# Flyback.net
KiCad netlist of a schematic drawn in Altium Designer
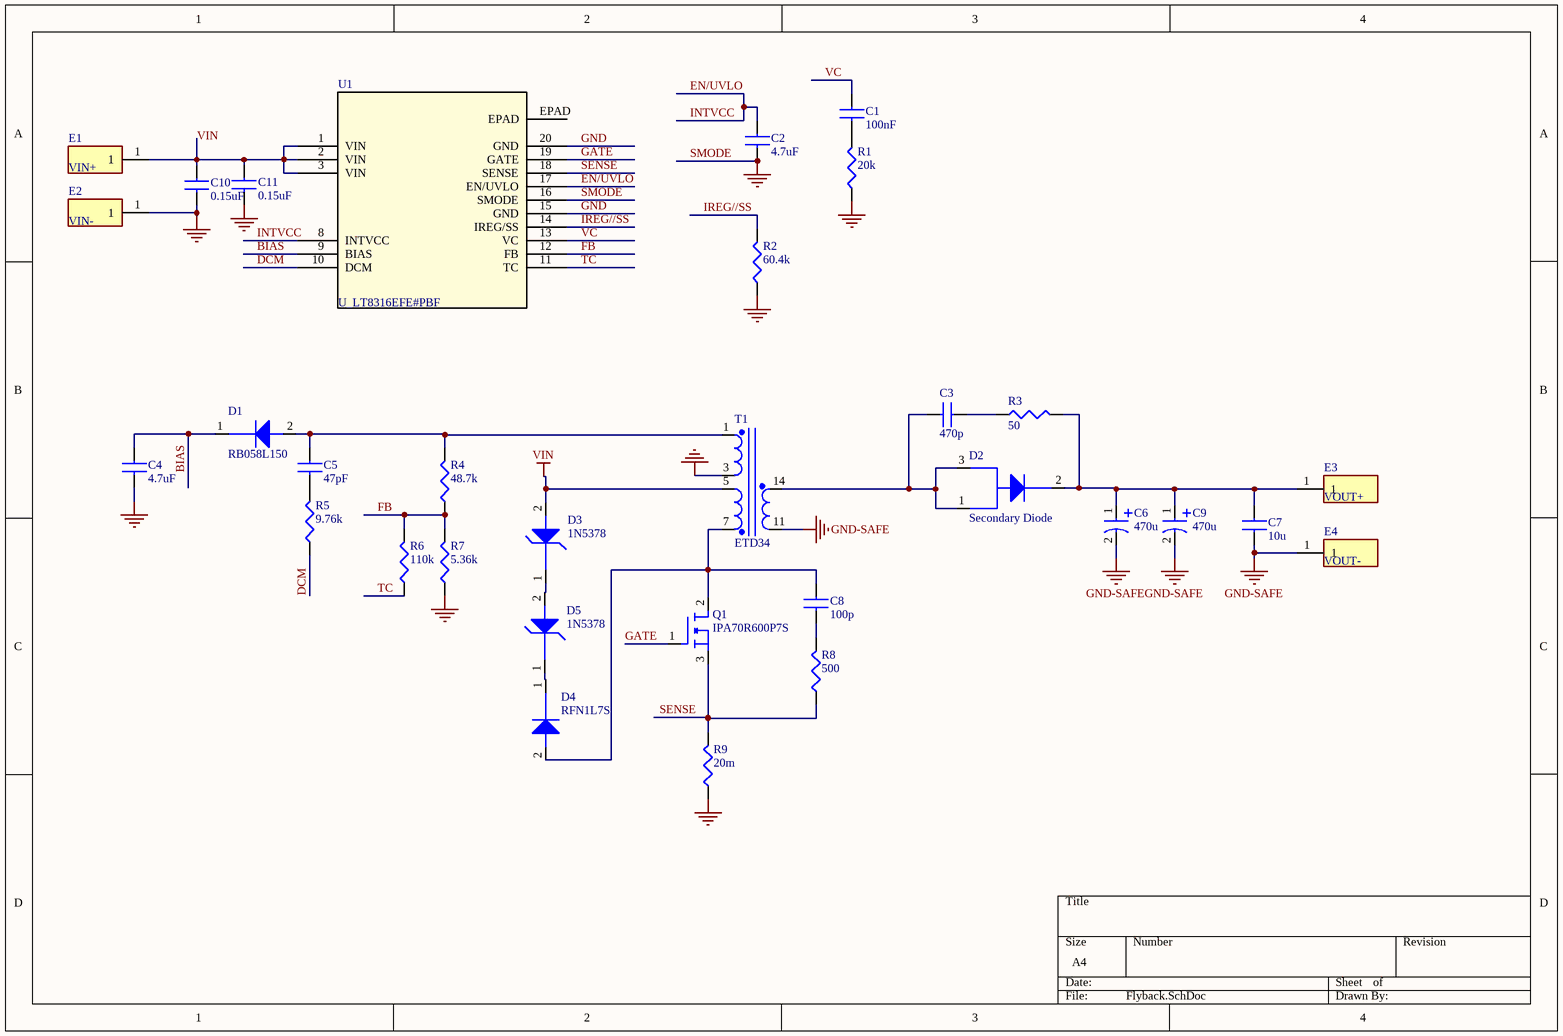
[diagram p0: Flyback.SchDoc]

(export (version "E")
  (design (tool "Eeschema 10.0.6"))
  (components
    (comp (ref "C1")
      (value "100nF")
      (footprint "C0402")
      (description "CAP CER 0.1UF 25V X7R 0402\r\nGRM155R71E104KE14J")
      (fields
        (field (name "MANUFACTURER") "Murata")
        (field (name "MANUFACTURER PART NUMBER") "GRM155R71E104KE14J")
      )
      (libsource (lib "Flyback_Schlib") (part "C_Vc"))
    )
    (comp (ref "C2")
      (value "4.7uF")
      (footprint "C0805")
      (description "CAP CER 4.7UF 25V X5R 0805\r\nGRM219R61E475MA73D")
      (fields
        (field (name "MANUFACTURER") "Murata")
        (field (name "MANUFACTURER PART NUMBER") "GRM219R61E475MA73D")
      )
      (libsource (lib "Flyback_Schlib") (part "C_IntVcc"))
    )
    (comp (ref "C3")
      (value "470p")
      (footprint "C0402")
      (description "Cap Ceramic 470pF 100V X7R 10% SMD 0402 125C Paper T/R\r\nGRM155R72A471KA01D")
      (fields
        (field (name "MANUFACTURER") "Murata")
        (field (name "MANUFACTURER PART NUMBER") "GRM155R72A471KA01D")
      )
      (libsource (lib "Flyback_Schlib") (part "C_Snub_Sec"))
    )
    (comp (ref "C4")
      (value "4.7uF")
      (footprint "C0805")
      (description "CAP CER 4.7UF 35V 10% X5R 0805\r\nGRM219R6YA475KA73D")
      (fields
        (field (name "MANUFACTURER") "Murata")
        (field (name "MANUFACTURER PART NUMBER") "GRM219R6YA475KA73D")
      )
      (libsource (lib "Flyback_Schlib") (part "C_Bias"))
    )
    (comp (ref "C5")
      (value "47pF")
      (footprint "C0603")
      (fields
        (field (name "MANUFACTURER") "Murata")
        (field (name "MANUFACTURER PART NUMBER") "GRM1885C2A470JA01D")
        (field (name "TOLERANCE") "5%")
      )
      (libsource (lib "Flyback_Schlib") (part "C_DCM"))
    )
    (comp (ref "C6")
      (value "470u")
      (footprint "C6.3x12")
      (description "Solid Polymer Aluminum, Radial, Output Capacitor\r\nA750EQ477M1CAAE015")
      (fields
        (field (name "MANUFACTURER") "KEMET")
        (field (name "MANUFACTURER PART NUMBER") "A750EQ477M1CAAE015")
      )
      (libsource (lib "Flyback_Schlib") (part "C_OUT_470u"))
    )
    (comp (ref "C7")
      (value "10u")
      (footprint "C0805")
      (fields
        (field (name "MANUFACTURER") "Murata")
        (field (name "MANUFACTURER PART NUMBER") "GRM21BR61E106MA73L")
        (field (name "TOLERANCE") "20%")
      )
      (libsource (lib "Flyback_Schlib") (part "C_OUT_10u"))
    )
    (comp (ref "C8")
      (value "100p")
      (footprint "C1206")
      (description "CAP CER 100PF 630V C0G/NP0 1206\r\nGRM31A5C2J101JW01D")
      (fields
        (field (name "MANUFACTURER") "Murata")
        (field (name "MANUFACTURER PART NUMBER") "GRM31A5C2J101JW01D")
      )
      (libsource (lib "Flyback_Schlib") (part "C_Snub_Pri"))
    )
    (comp (ref "C9")
      (value "470u")
      (footprint "C6.3x12")
      (description "Solid Polymer Aluminum, Radial, Output Capacitor\r\nA750EQ477M1CAAE015")
      (fields
        (field (name "MANUFACTURER") "KEMET")
        (field (name "MANUFACTURER PART NUMBER") "A750EQ477M1CAAE015")
      )
      (libsource (lib "Flyback_Schlib") (part "C_OUT_470u"))
    )
    (comp (ref "C10")
      (value "0.15uF")
      (footprint "C1210")
      (description "CAP CER 0.15UF 500V X7R 1210\r\nC1210C154KCRACTU")
      (fields
        (field (name "MANUFACTURER") "KEMET")
        (field (name "MANUFACTURER PART NUMBER") "C1210C154KCRACTU")
      )
      (libsource (lib "Flyback_Schlib") (part "C_Input"))
    )
    (comp (ref "C11")
      (value "0.15uF")
      (footprint "C1210")
      (description "CAP CER 0.15UF 500V X7R 1210\r\nC1210C154KCRACTU")
      (fields
        (field (name "MANUFACTURER") "KEMET")
        (field (name "MANUFACTURER PART NUMBER") "C1210C154KCRACTU")
      )
      (libsource (lib "Flyback_Schlib") (part "C_Input"))
    )
    (comp (ref "D1")
      (value "RB058L150")
      (footprint "SOD128")
      (description "Schottky Barrier Diode for general rectification Diode for Bias Pin")
      (fields (field (name "MANUFACTURER") "Rohm") (field (name "MANUFACTURER PART NUMBER") "RB058LAM150TR"))
      (libsource (lib "Flyback_Schlib") (part "D_RB058LAM150TR"))
    )
    (comp (ref "D2")
      (value "Secondary Diode")
      (footprint "TO220AB")
      (description "Diode Schottky 120V 20A 3-Pin(3+Tab) TO-220AB Tube")
      (fields
        (field (name "MANUFACTURER") "STMicroelectronics")
        (field (name "MANUFACTURER PART NUMBER") "STPS20SM120ST")
      )
      (libsource (lib "Flyback_Schlib") (part "D_STPS20SM120ST"))
    )
    (comp (ref "D3")
      (value "1N5378")
      (footprint "D017AA")
      (description "DIODE ZENER 100V 5W AXIAL\r\n1N5378BG")
      (fields
        (field (name "MANUFACTURER") "ON Semiconductor")
        (field (name "MANUFACTURER PART NUMBER") "1N5378BG")
      )
      (libsource (lib "Flyback_Schlib") (part "D_1N5378BG"))
    )
    (comp (ref "D4")
      (value "RFN1L7S")
      (footprint "DO214_AC_SMA")
      (description "Clamp circuit fast diode")
      (fields (field (name "MANUFACTURER") "Rohm") (field (name "MANUFACTURER PART NUMBER") "RFN1L7SDDTE25"))
      (libsource (lib "Flyback_Schlib") (part "D_RFN1L7SDDTE25"))
    )
    (comp (ref "D5")
      (value "1N5378")
      (footprint "D017AA")
      (description "DIODE ZENER 100V 5W AXIAL\r\n1N5378BG")
      (fields
        (field (name "MANUFACTURER") "ON Semiconductor")
        (field (name "MANUFACTURER PART NUMBER") "1N5378BG")
      )
      (libsource (lib "Flyback_Schlib") (part "D_1N5378BG"))
    )
    (comp (ref "E1")
      (value "VIN+")
      (footprint "MILMAX_2501-2-00-80-00-00-07-0")
      (description "TERM TURRET SINGLE L=5.56MM TIN\r\n2501-2-00-80-00-00-07-0")
      (fields
        (field (name "MANUFACTURER") "Mill-Max")
        (field (name "MANUFACTURER PART NUMBER") "2501-2-00-80-00-00-07-0")
      )
      (libsource (lib "Flyback_Schlib") (part "Connector"))
    )
    (comp (ref "E2")
      (value "VIN-")
      (footprint "MILMAX_2501-2-00-80-00-00-07-0")
      (description "TERM TURRET SINGLE L=5.56MM TIN\r\n2501-2-00-80-00-00-07-0")
      (fields
        (field (name "MANUFACTURER") "Mill-Max")
        (field (name "MANUFACTURER PART NUMBER") "2501-2-00-80-00-00-07-0")
      )
      (libsource (lib "Flyback_Schlib") (part "Connector"))
    )
    (comp (ref "E3")
      (value "VOUT+")
      (footprint "MILMAX_2501-2-00-80-00-00-07-0")
      (description "TERM TURRET SINGLE L=5.56MM TIN\r\n2501-2-00-80-00-00-07-0")
      (fields
        (field (name "MANUFACTURER") "Mill-Max")
        (field (name "MANUFACTURER PART NUMBER") "2501-2-00-80-00-00-07-0")
      )
      (libsource (lib "") (part "Connector_1"))
    )
    (comp (ref "E4")
      (value "VOUT-")
      (footprint "MILMAX_2501-2-00-80-00-00-07-0")
      (description "TERM TURRET SINGLE L=5.56MM TIN\r\n2501-2-00-80-00-00-07-0")
      (fields
        (field (name "MANUFACTURER") "Mill-Max")
        (field (name "MANUFACTURER PART NUMBER") "2501-2-00-80-00-00-07-0")
      )
      (libsource (lib "") (part "Connector_1"))
    )
    (comp (ref "Q1")
      (value "IPA70R600P7S")
      (footprint "TO220_FullPAK")
      (description "Single N-Channel 700V 600 mOhm 10.5 nC CoolMOS Power Mosfet - TO-220-3FP")
      (fields
        (field (name "MANUFACTURER") "Infineon")
        (field (name "MANUFACTURER PART NUMBER") "IPA70R600P7SXKSA1")
      )
      (libsource (lib "Flyback_Schlib") (part "Q_IPA70R600P7SXKSA1"))
    )
    (comp (ref "R1")
      (value "20k")
      (footprint "R0603")
      (description "D11/CRCW0603-C 100 20K 1% ET1\r\nCRCW060320K0FKEAC")
      (fields
        (field (name "MANUFACTURER") "Vishay")
        (field (name "MANUFACTURER PART NUMBER") "CRCW060320K0FKEAC")
      )
      (libsource (lib "Flyback_Schlib") (part "R_CVc"))
    )
    (comp (ref "R2")
      (value "60.4k")
      (footprint "R0603")
      (fields
        (field (name "MANUFACTURER") "Vishay")
        (field (name "MANUFACTURER PART NUMBER") "CRCW060360K4FKEA")
        (field (name "TOLERANCE") "1%")
      )
      (libsource (lib "Flyback_Schlib") (part "R_IREG//SS"))
    )
    (comp (ref "R3")
      (value "50")
      (footprint "R0603")
      (fields
        (field (name "MANUFACTURER") "Vishay Dale")
        (field (name "MANUFACTURER PART NUMBER") "CRCW060349R9FKEAHP")
        (field (name "TOLERANCE") "1%")
      )
      (libsource (lib "Flyback_Schlib") (part "R_Snubber_Sec"))
    )
    (comp (ref "R4")
      (value "48.7k")
      (footprint "R0603")
      (description "Res Thick Film 0603 48.7K Ohm 1% 0.1W(1/10W) ±100ppm/C Pad SMD Automotive T/R\r\nCRCW060348K7FKEA")
      (fields
        (field (name "MANUFACTURER") "Vishay")
        (field (name "MANUFACTURER PART NUMBER") "CRCW060348K7FKEA")
      )
      (libsource (lib "Flyback_Schlib") (part "R_FB1"))
    )
    (comp (ref "R5")
      (value "9.76k")
      (footprint "R0603")
      (fields
        (field (name "MANUFACTURER") "Vishay")
        (field (name "MANUFACTURER PART NUMBER") "CRCW06039K76FKEA")
        (field (name "TOLERANCE") "1%")
      )
      (libsource (lib "Flyback_Schlib") (part "R_DCM"))
    )
    (comp (ref "R6")
      (value "110k")
      (footprint "R0603")
      (description "RES SMD 110K OHM 5% 1/10W 0603\r\nCRCW0603110KJNEA")
      (fields
        (field (name "MANUFACTURER") "Vishay Dale")
        (field (name "MANUFACTURER PART NUMBER") "CRCW0603110KJNEA")
      )
      (libsource (lib "Flyback_Schlib") (part "R_Tc"))
    )
    (comp (ref "R7")
      (value "5.36k")
      (footprint "R0603")
      (fields
        (field (name "MANUFACTURER") "Vishay")
        (field (name "MANUFACTURER PART NUMBER") "CRCW06035K36FKEA")
        (field (name "TOLERANCE") "1%")
      )
      (libsource (lib "Flyback_Schlib") (part "R_FB2"))
    )
    (comp (ref "R8")
      (value "500")
      (footprint "R2512")
      (description "Res Thick Film 2512 499 Ohm 1% 2W ±100ppm/°C Molded SMD SMD Paper T/R\r\nCRM2512-FX-4990ELF")
      (fields
        (field (name "MANUFACTURER") "Bourns")
        (field (name "MANUFACTURER PART NUMBER") "CRM2512-FX-4990ELF")
      )
      (libsource (lib "Flyback_Schlib") (part "R_Snubber_Pri"))
    )
    (comp (ref "R9")
      (value "20m")
      (footprint "R1220")
      (description "TR / Current Sensors, 0805 0.25W, 5%\r\nRL1220T-R020-J")
      (fields
        (field (name "MANUFACTURER") "Susumu")
        (field (name "MANUFACTURER PART NUMBER") "RL1220T-R020-J")
      )
      (libsource (lib "Flyback_Schlib") (part "R_Sense"))
    )
    (comp (ref "T1")
      (value "ETD34")
      (footprint "ETD34_CoilFormer")
      (description "Epcos B66362W1014T001 ETD 34 Coil Former, 14 Pins\r\nB66362W1014T001")
      (fields
        (field (name "MANUFACTURER") "TDK EPCOS")
        (field (name "MANUFACTURER PART NUMBER") "B66362W1014T001")
      )
      (libsource (lib "Flyback_Schlib") (part "Transformer_CoilFormer"))
    )
    (comp (ref "U1")
      (value "U_LT8316EFE#PBF")
      (footprint "LT8316EFE")
      (description "DC/DC Cntrlr Single-OUT 142kHz Automotive 16-Pin TSSOP EP Tube")
      (fields
        (field (name "MANUFACTURER") "Analog Devices / Linear Technology")
        (field (name "MANUFACTURER PART NUMBER") "LT8316EFE#PBF")
      )
      (libsource (lib "Flyback_Schlib") (part "U_LT8316EFE#PBF"))
    )
  )
  (nets
    (net (code "1") (name "/BIAS") (class "Default")
      (node (ref "C4") (pin "2") (pinfunction "2_2") (pintype "passive"))
      (node (ref "D1") (pin "1") (pinfunction "1_1") (pintype "passive"))
      (node (ref "U1") (pin "9") (pinfunction "BIAS_9") (pintype "passive"))
    )
    (net (code "2") (name "/DCM") (class "Default")
      (node (ref "R5") (pin "1") (pinfunction "1_1") (pintype "passive"))
      (node (ref "U1") (pin "10") (pinfunction "DCM_10") (pintype "passive"))
    )
    (net (code "3") (name "/EN{slash}UVLO") (class "Default")
      (node (ref "C2") (pin "2") (pinfunction "2_2") (pintype "passive"))
      (node (ref "U1") (pin "17") (pinfunction "EN/UVLO_17") (pintype "passive"))
      (node (ref "U1") (pin "8") (pinfunction "INTVCC_8") (pintype "passive"))
    )
    (net (code "4") (name "/FB") (class "Default")
      (node (ref "R4") (pin "1") (pinfunction "1_1") (pintype "passive"))
      (node (ref "R6") (pin "2") (pinfunction "2_2") (pintype "passive"))
      (node (ref "R7") (pin "2") (pinfunction "2_2") (pintype "passive"))
      (node (ref "U1") (pin "12") (pinfunction "FB_12") (pintype "passive"))
    )
    (net (code "5") (name "/GATE") (class "Default")
      (node (ref "Q1") (pin "1") (pinfunction "1_1") (pintype "passive"))
      (node (ref "U1") (pin "19") (pinfunction "GATE_19") (pintype "passive"))
    )
    (net (code "6") (name "/IREG{slash}{slash}SS") (class "Default")
      (node (ref "R2") (pin "2") (pinfunction "2_2") (pintype "passive"))
      (node (ref "U1") (pin "14") (pinfunction "IREG/SS_14") (pintype "passive"))
    )
    (net (code "7") (name "/SENSE") (class "Default")
      (node (ref "Q1") (pin "3") (pinfunction "3_3") (pintype "passive"))
      (node (ref "R8") (pin "1") (pinfunction "1_1") (pintype "passive"))
      (node (ref "R9") (pin "2") (pinfunction "2_2") (pintype "passive"))
      (node (ref "U1") (pin "18") (pinfunction "SENSE_18") (pintype "passive"))
    )
    (net (code "8") (name "/TC") (class "Default")
      (node (ref "R6") (pin "1") (pinfunction "1_1") (pintype "passive"))
      (node (ref "U1") (pin "11") (pinfunction "TC_11") (pintype "passive"))
    )
    (net (code "9") (name "/VC") (class "Default")
      (node (ref "C1") (pin "2") (pinfunction "2_2") (pintype "passive"))
      (node (ref "U1") (pin "13") (pinfunction "VC_13") (pintype "passive"))
    )
    (net (code "10") (name "GND") (class "Default")
      (node (ref "C10") (pin "1") (pinfunction "1_1") (pintype "passive"))
      (node (ref "C11") (pin "1") (pinfunction "1_1") (pintype "passive"))
      (node (ref "C2") (pin "1") (pinfunction "1_1") (pintype "passive"))
      (node (ref "C4") (pin "1") (pinfunction "1_1") (pintype "passive"))
      (node (ref "E2") (pin "1") (pinfunction "1_1") (pintype "passive"))
      (node (ref "R1") (pin "1") (pinfunction "1_1") (pintype "passive"))
      (node (ref "R2") (pin "1") (pinfunction "1_1") (pintype "passive"))
      (node (ref "R7") (pin "1") (pinfunction "1_1") (pintype "passive"))
      (node (ref "R9") (pin "1") (pinfunction "1_1") (pintype "passive"))
      (node (ref "T1") (pin "3") (pinfunction "3_3") (pintype "passive"))
      (node (ref "U1") (pin "15") (pinfunction "GND_15") (pintype "passive"))
      (node (ref "U1") (pin "16") (pinfunction "SMODE_16") (pintype "passive"))
      (node (ref "U1") (pin "20") (pinfunction "GND_20") (pintype "passive"))
    )
    (net (code "11") (name "GND-SAFE") (class "Default")
      (node (ref "C6") (pin "2") (pinfunction "2_2") (pintype "passive"))
      (node (ref "C7") (pin "1") (pinfunction "1_1") (pintype "passive"))
      (node (ref "C9") (pin "2") (pinfunction "2_2") (pintype "passive"))
      (node (ref "E4") (pin "1") (pinfunction "1_1") (pintype "passive"))
      (node (ref "T1") (pin "11") (pinfunction "11_11") (pintype "passive"))
    )
    (net (code "12") (name "Net-(C1-Pad1)") (class "Default")
      (node (ref "C1") (pin "1") (pinfunction "1_1") (pintype "passive"))
      (node (ref "R1") (pin "2") (pinfunction "2_2") (pintype "passive"))
    )
    (net (code "13") (name "Net-(C3-Pad1)") (class "Default")
      (node (ref "C3") (pin "1") (pinfunction "1_1") (pintype "passive"))
      (node (ref "D2") (pin "1") (pinfunction "1_1") (pintype "passive"))
      (node (ref "D2") (pin "3") (pinfunction "3_3") (pintype "passive"))
      (node (ref "T1") (pin "14") (pinfunction "11_14") (pintype "passive"))
    )
    (net (code "14") (name "Net-(C3-Pad2)") (class "Default")
      (node (ref "C3") (pin "2") (pinfunction "2_2") (pintype "passive"))
      (node (ref "R3") (pin "1") (pinfunction "1_1") (pintype "passive"))
    )
    (net (code "15") (name "Net-(C5-Pad1)") (class "Default")
      (node (ref "C5") (pin "1") (pinfunction "1_1") (pintype "passive"))
      (node (ref "R5") (pin "2") (pinfunction "2_2") (pintype "passive"))
    )
    (net (code "16") (name "Net-(C5-Pad2)") (class "Default")
      (node (ref "C5") (pin "2") (pinfunction "2_2") (pintype "passive"))
      (node (ref "D1") (pin "2") (pinfunction "2_2") (pintype "passive"))
      (node (ref "R4") (pin "2") (pinfunction "2_2") (pintype "passive"))
      (node (ref "T1") (pin "1") (pinfunction "1_1") (pintype "passive"))
    )
    (net (code "17") (name "Net-(C6-Pad1)") (class "Default")
      (node (ref "C6") (pin "1") (pinfunction "1_1") (pintype "passive"))
      (node (ref "C7") (pin "2") (pinfunction "2_2") (pintype "passive"))
      (node (ref "C9") (pin "1") (pinfunction "1_1") (pintype "passive"))
      (node (ref "D2") (pin "2") (pinfunction "2_2") (pintype "passive"))
      (node (ref "E3") (pin "1") (pinfunction "1_1") (pintype "passive"))
      (node (ref "R3") (pin "2") (pinfunction "2_2") (pintype "passive"))
    )
    (net (code "18") (name "Net-(C8-Pad1)") (class "Default")
      (node (ref "C8") (pin "1") (pinfunction "1_1") (pintype "passive"))
      (node (ref "R8") (pin "2") (pinfunction "2_2") (pintype "passive"))
    )
    (net (code "19") (name "Net-(C8-Pad2)") (class "Default")
      (node (ref "C8") (pin "2") (pinfunction "2_2") (pintype "passive"))
      (node (ref "D4") (pin "2") (pinfunction "2_2") (pintype "passive"))
      (node (ref "Q1") (pin "2") (pinfunction "2_2") (pintype "passive"))
      (node (ref "T1") (pin "7") (pinfunction "7_7") (pintype "passive"))
    )
    (net (code "20") (name "Net-(D3-Pad1)") (class "Default")
      (node (ref "D3") (pin "1") (pinfunction "1_1") (pintype "passive"))
      (node (ref "D5") (pin "2") (pinfunction "2_2") (pintype "passive"))
    )
    (net (code "21") (name "Net-(D4-Pad1)") (class "Default")
      (node (ref "D4") (pin "1") (pinfunction "1_1") (pintype "passive"))
      (node (ref "D5") (pin "1") (pinfunction "1_1") (pintype "passive"))
    )
    (net (code "22") (name "VIN") (class "Default")
      (node (ref "C10") (pin "2") (pinfunction "2_2") (pintype "passive"))
      (node (ref "C11") (pin "2") (pinfunction "2_2") (pintype "passive"))
      (node (ref "D3") (pin "2") (pinfunction "2_2") (pintype "passive"))
      (node (ref "E1") (pin "1") (pinfunction "1_1") (pintype "passive"))
      (node (ref "T1") (pin "5") (pinfunction "5_5") (pintype "passive"))
      (node (ref "U1") (pin "1") (pinfunction "VIN_1") (pintype "passive"))
      (node (ref "U1") (pin "2") (pinfunction "VIN_2") (pintype "passive"))
      (node (ref "U1") (pin "3") (pinfunction "VIN_3") (pintype "passive"))
    )
    (net (code "23") (name "unconnected-(U1-PadEPAD)") (class "Default")
      (node (ref "U1") (pin "EPAD") (pinfunction "EPAD_EPAD") (pintype "passive"))
    )
  )
)
